# ProPrj_piezoAmpBoard_2024-09-30.net
KiCad netlist of a schematic drawn in EasyEDA Pro
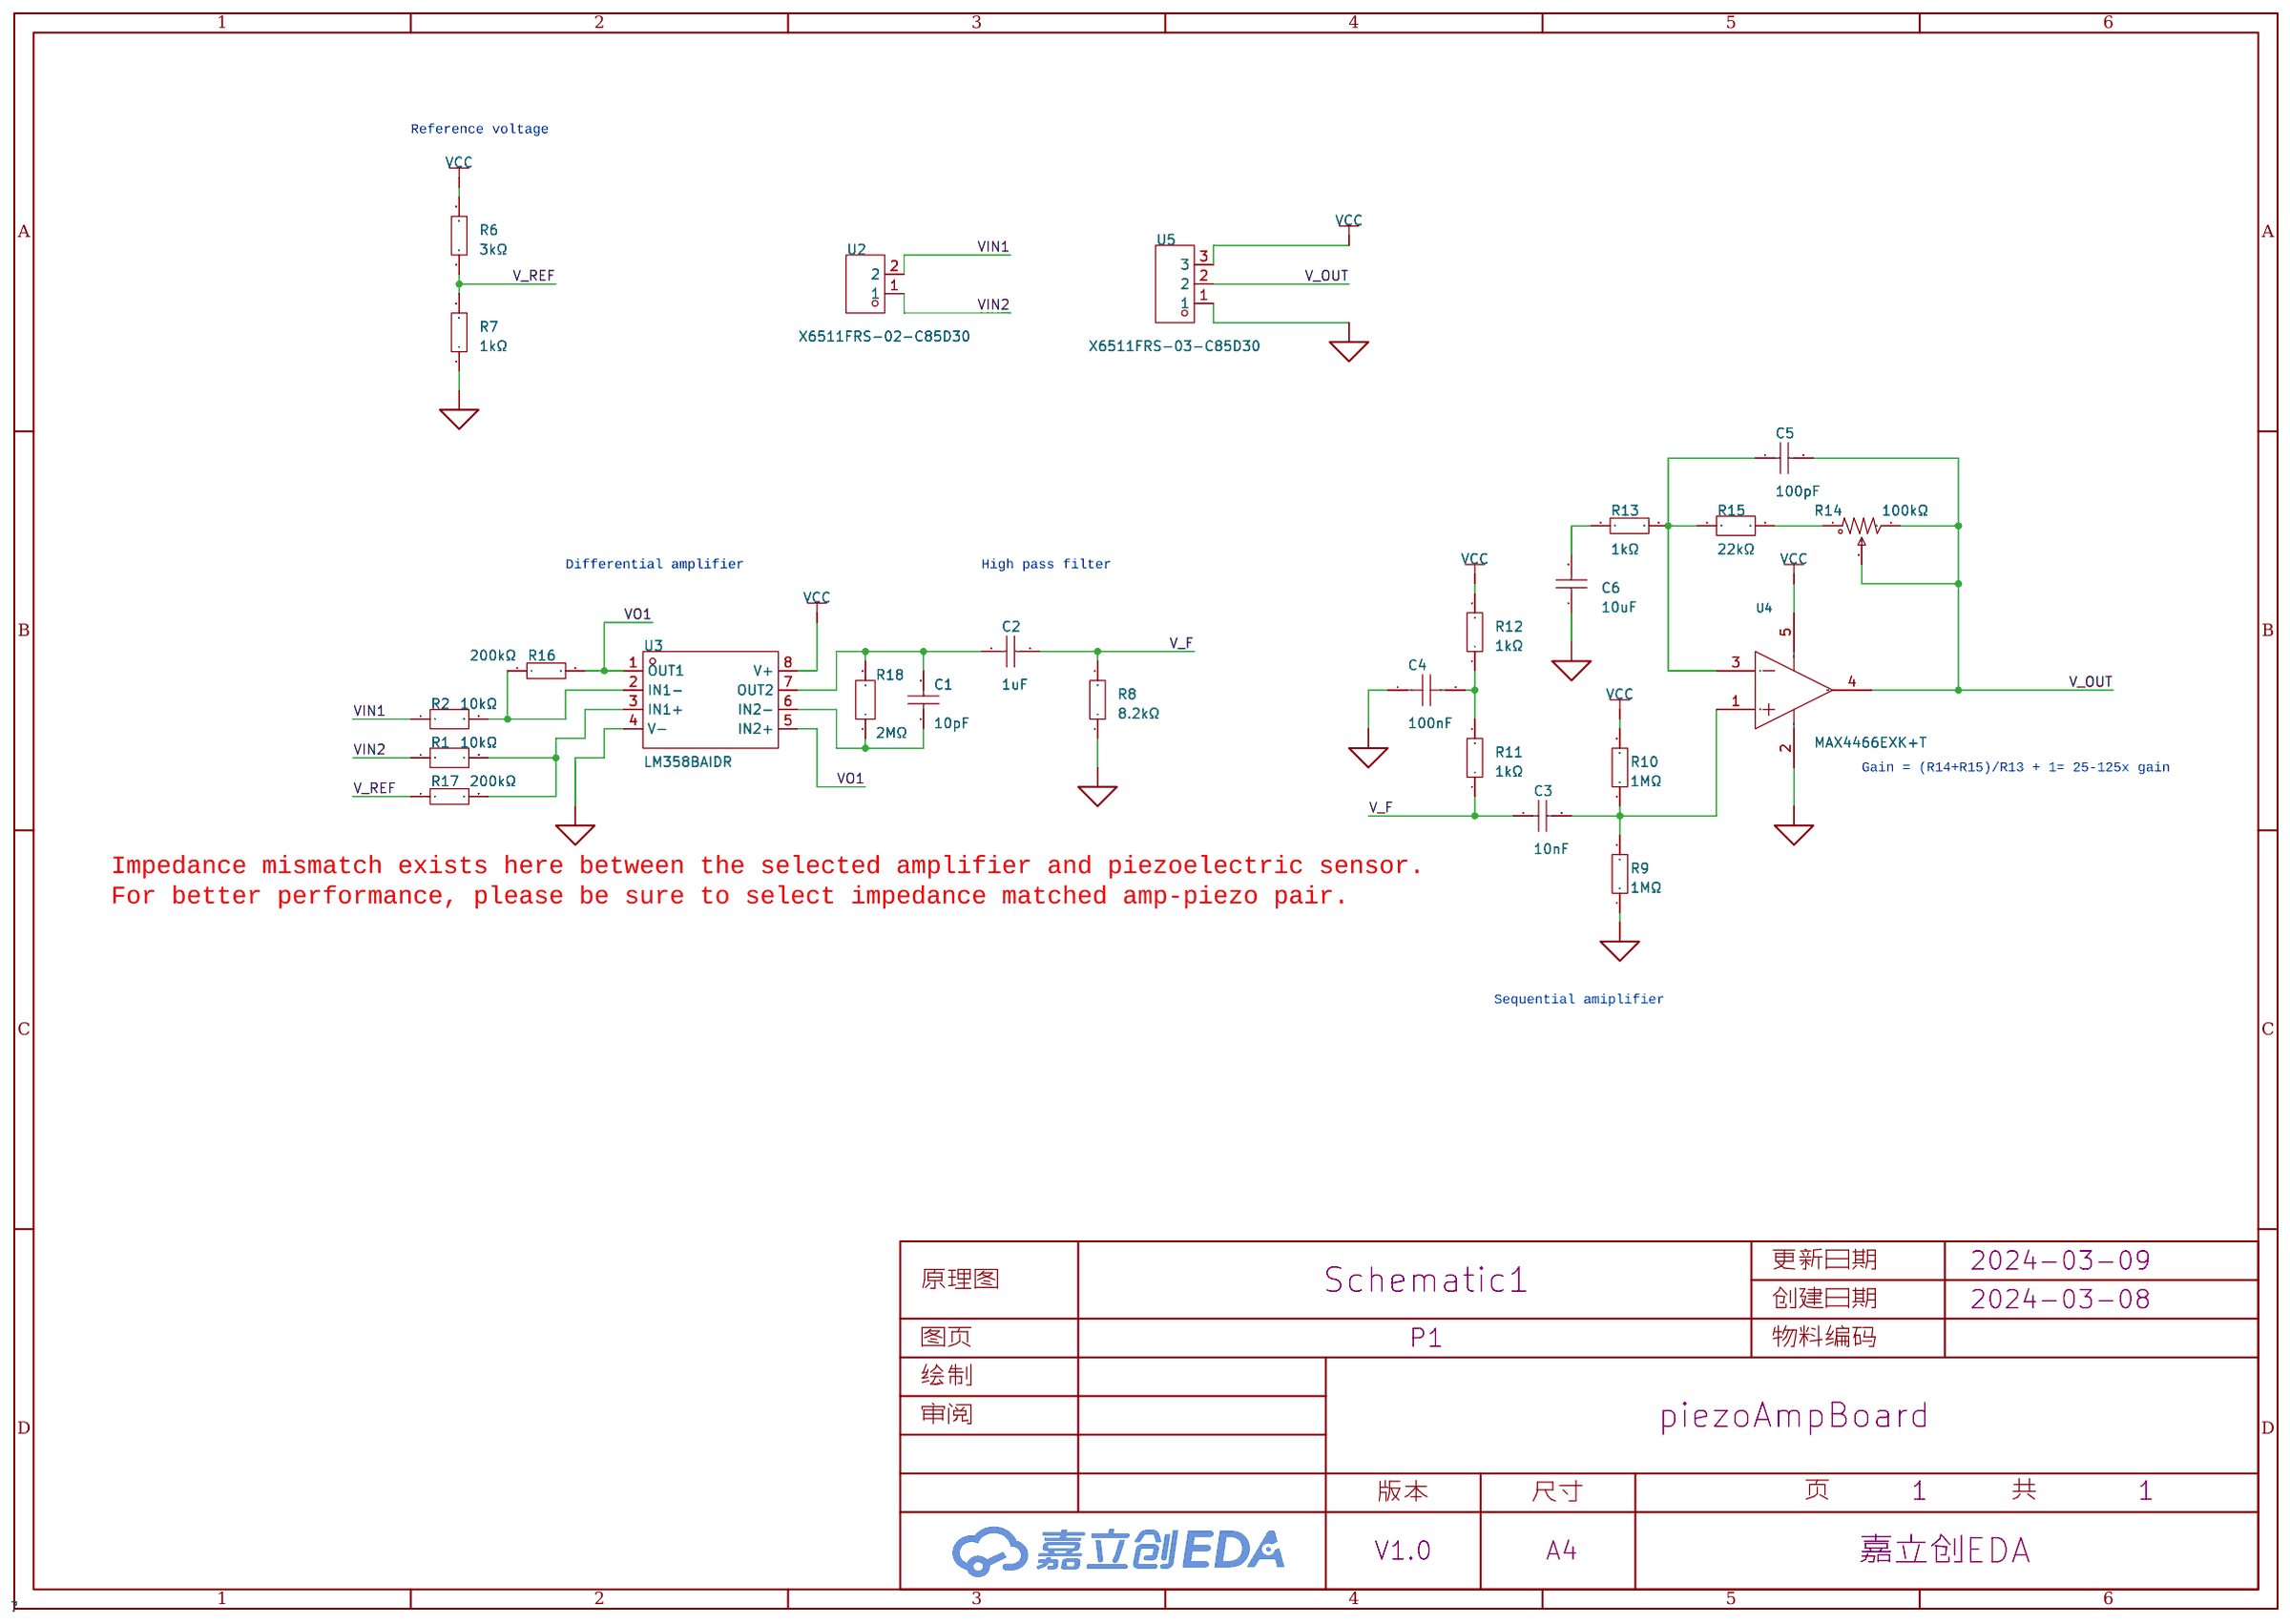
[diagram p0: schematic sheet]

(export (version "E")
  (design (tool "Eeschema 10.0.6"))
  (components
    (comp (ref "C1")
      (value "10pF")
      (footprint "easyedapro:C0402")
      (description "容值:10pF;精度:±5%;额定电压:50V;材质(温度系数):NP0;")
      (fields
        (field (name "Manufacturer Part") "CC0402JRNPO9BN100")
        (field (name "Manufacturer") "YAGEO(国巨)")
      )
      (libsource (lib "easyedapro") (part "CC0402JRNPO9BN100"))
    )
    (comp (ref "C2")
      (value "1uF")
      (footprint "easyedapro:C0402")
      (description "容值:1uF;精度:±10%;额定电压:10V;材质(温度系数):X5R;")
      (fields
        (field (name "Manufacturer Part") "CL05A105KP5NNNC")
        (field (name "Manufacturer") "SAMSUNG(三星)")
      )
      (libsource (lib "easyedapro") (part "CL05A105KP5NNNC"))
    )
    (comp (ref "C3")
      (value "10nF")
      (footprint "easyedapro:C0402")
      (description "容值:10nF;精度:±10%;额定电压:50V;材质(温度系数):X7R;")
      (fields
        (field (name "Manufacturer Part") "CC0402KRX7R9BB103")
        (field (name "Manufacturer") "YAGEO(国巨)")
      )
      (libsource (lib "easyedapro") (part "CC0402KRX7R9BB103"))
    )
    (comp (ref "C4")
      (value "100nF")
      (footprint "easyedapro:C0402")
      (description "容值:100nF;精度:±10%;额定电压:16V;材质(温度系数):X7R;")
      (fields
        (field (name "Manufacturer Part") "CC0402KRX7R7BB104")
        (field (name "Manufacturer") "YAGEO(国巨)")
      )
      (libsource (lib "easyedapro") (part "CC0402KRX7R7BB104"))
    )
    (comp (ref "C5")
      (value "100pF")
      (footprint "easyedapro:C0402")
      (description "容值:100pF;精度:±5%;额定电压:50V;材质(温度系数):C0G;")
      (fields
        (field (name "Manufacturer Part") "GRM1555C1H101JA01D")
        (field (name "Manufacturer") "muRata(村田)")
      )
      (libsource (lib "easyedapro") (part "GRM1555C1H101JA01D"))
    )
    (comp (ref "C6")
      (value "10uF")
      (footprint "easyedapro:C0402")
      (description "容值:10uF;精度:±20%;额定电压:6.3V;材质(温度系数):X5R;")
      (fields
        (field (name "Manufacturer Part") "GRM155R60J106ME44D")
        (field (name "Manufacturer") "muRata(村田)")
      )
      (libsource (lib "easyedapro") (part "GRM155R60J106ME44D"))
    )
    (comp (ref "R1")
      (value "10kΩ")
      (footprint "easyedapro:R0201")
      (description "电阻类型:厚膜电阻;阻值:10kΩ;精度:±1%;功率:50mW;最大工作电压:25V;温度系数:±200ppm/°C;")
      (fields
        (field (name "Manufacturer Part") "0201WMF1002TEE")
        (field (name "Manufacturer") "UNI-ROYAL(厚声)")
      )
      (libsource (lib "easyedapro") (part "0201WMF1002TEE"))
    )
    (comp (ref "R2")
      (value "10kΩ")
      (footprint "easyedapro:R0201")
      (description "电阻类型:厚膜电阻;阻值:10kΩ;精度:±1%;功率:50mW;最大工作电压:25V;温度系数:±200ppm/°C;")
      (fields
        (field (name "Manufacturer Part") "0201WMF1002TEE")
        (field (name "Manufacturer") "UNI-ROYAL(厚声)")
      )
      (libsource (lib "easyedapro") (part "0201WMF1002TEE"))
    )
    (comp (ref "R6")
      (value "3kΩ")
      (footprint "easyedapro:R0402")
      (description "电阻类型:厚膜电阻;阻值:3kΩ;精度:±1%;功率:62.5mW;最大工作电压:50V;温度系数:±100ppm/°C;")
      (fields
        (field (name "Manufacturer Part") "0402WGF3001TCE")
        (field (name "Manufacturer") "UNI-ROYAL(厚声)")
      )
      (libsource (lib "easyedapro") (part "0402WGF3001TCE"))
    )
    (comp (ref "R7")
      (value "1kΩ")
      (footprint "easyedapro:R0402")
      (description "电阻类型:厚膜电阻;阻值:1kΩ;精度:±1%;功率:62.5mW;最大工作电压:50V;温度系数:±100ppm/°C;")
      (fields
        (field (name "Manufacturer Part") "0402WGF1001TCE")
        (field (name "Manufacturer") "UNI-ROYAL(厚声)")
      )
      (libsource (lib "easyedapro") (part "0402WGF1001TCE"))
    )
    (comp (ref "R8")
      (value "8.2kΩ")
      (footprint "easyedapro:R0402")
      (description "电阻类型:厚膜电阻;阻值:8.2kΩ;精度:±1%;功率:62.5mW;最大工作电压:50V;温度系数:±100ppm/°C;")
      (fields
        (field (name "Manufacturer Part") "0402WGF8201TCE")
        (field (name "Manufacturer") "UNI-ROYAL(厚声)")
      )
      (libsource (lib "easyedapro") (part "0402WGF8201TCE"))
    )
    (comp (ref "R9")
      (value "1MΩ")
      (footprint "easyedapro:R0201")
      (description "电阻类型:厚膜电阻;阻值:1MΩ;精度:±1%;功率:50mW;最大工作电压:25V;温度系数:±200ppm/°C;")
      (fields (field (name "Manufacturer Part") "RC0201FR-071ML") (field (name "Manufacturer") "YAGEO(国巨)"))
      (libsource (lib "easyedapro") (part "RC0201FR-071ML"))
    )
    (comp (ref "R10")
      (value "1MΩ")
      (footprint "easyedapro:R0201")
      (description "电阻类型:厚膜电阻;阻值:1MΩ;精度:±1%;功率:50mW;最大工作电压:25V;温度系数:±200ppm/°C;")
      (fields (field (name "Manufacturer Part") "RC0201FR-071ML") (field (name "Manufacturer") "YAGEO(国巨)"))
      (libsource (lib "easyedapro") (part "RC0201FR-071ML"))
    )
    (comp (ref "R11")
      (value "1kΩ")
      (footprint "easyedapro:R0201")
      (description "电阻类型:厚膜电阻;阻值:1kΩ;精度:±1%;功率:50mW;最大工作电压:25V;温度系数:±200ppm/°C;")
      (fields
        (field (name "Manufacturer Part") "0201WMF1001TEE")
        (field (name "Manufacturer") "UNI-ROYAL(厚声)")
      )
      (libsource (lib "easyedapro") (part "0201WMF1001TEE"))
    )
    (comp (ref "R12")
      (value "1kΩ")
      (footprint "easyedapro:R0201")
      (description "电阻类型:厚膜电阻;阻值:1kΩ;精度:±1%;功率:50mW;最大工作电压:25V;温度系数:±200ppm/°C;")
      (fields
        (field (name "Manufacturer Part") "0201WMF1001TEE")
        (field (name "Manufacturer") "UNI-ROYAL(厚声)")
      )
      (libsource (lib "easyedapro") (part "0201WMF1001TEE"))
    )
    (comp (ref "R13")
      (value "1kΩ")
      (footprint "easyedapro:R0201")
      (description "电阻类型:厚膜电阻;阻值:1kΩ;精度:±1%;功率:50mW;最大工作电压:25V;温度系数:±200ppm/°C;")
      (fields
        (field (name "Manufacturer Part") "0201WMF1001TEE")
        (field (name "Manufacturer") "UNI-ROYAL(厚声)")
      )
      (libsource (lib "easyedapro") (part "0201WMF1001TEE"))
    )
    (comp (ref "R14")
      (value "100kΩ")
      (footprint "easyedapro:RES-ADJ-SMD_TC33X-2-104E")
      (description "阻值:100kΩ;精度:±25%;功率:150mW;温度系数:±250ppm/°C;")
      (fields (field (name "Manufacturer Part") "TC33X-2-104E") (field (name "Manufacturer") "BOURNS"))
      (libsource (lib "easyedapro") (part "TC33X-2-104E"))
    )
    (comp (ref "R15")
      (value "22kΩ")
      (footprint "easyedapro:R0201")
      (description "电阻类型:厚膜电阻;阻值:22kΩ;精度:±1%;功率:50mW;最大工作电压:25V;温度系数:±200ppm/°C;")
      (fields (field (name "Manufacturer Part") "RC0201FR-0722KL") (field (name "Manufacturer") "YAGEO(国巨)"))
      (libsource (lib "easyedapro") (part "RC0201FR-0722KL"))
    )
    (comp (ref "R16")
      (value "200kΩ")
      (footprint "easyedapro:R0201")
      (description "电阻类型:厚膜电阻;阻值:200kΩ;精度:±1%;功率:50mW;最大工作电压:25V;温度系数:±200ppm/°C;")
      (fields (field (name "Manufacturer Part") "RC0201FR-07200KL") (field (name "Manufacturer") "YAGEO(国巨)"))
      (libsource (lib "easyedapro") (part "RC0201FR-07200KL"))
    )
    (comp (ref "R17")
      (value "200kΩ")
      (footprint "easyedapro:R0201")
      (description "电阻类型:厚膜电阻;阻值:200kΩ;精度:±1%;功率:50mW;最大工作电压:25V;温度系数:±200ppm/°C;")
      (fields (field (name "Manufacturer Part") "RC0201FR-07200KL") (field (name "Manufacturer") "YAGEO(国巨)"))
      (libsource (lib "easyedapro") (part "RC0201FR-07200KL"))
    )
    (comp (ref "R18")
      (value "2MΩ")
      (footprint "easyedapro:R0201")
      (description "电阻类型:厚膜电阻;阻值:2MΩ;精度:±1%;功率:50mW;最大工作电压:25V;温度系数:±200ppm/°C;")
      (fields
        (field (name "Manufacturer Part") "0201WMF2004TEE")
        (field (name "Manufacturer") "UNI-ROYAL(厚声)")
      )
      (libsource (lib "easyedapro") (part "0201WMF2004TEE"))
    )
    (comp (ref "U2")
      (value "X6511FRS-02-C85D30")
      (footprint "easyedapro:HDR-SMD_2P-P2.54-H-F-L11.5")
      (description "插孔结构:1x2P;间距:2.54mm;安装类型:卧贴;排数:单排;总孔位数:2P;塑高:8.5mm;")
      (fields (field (name "Manufacturer") "XKB Connectivity(中国星坤)"))
      (libsource (lib "easyedapro") (part "X6511FRS-02-C85D30"))
    )
    (comp (ref "U3")
      (value "LM358BAIDR")
      (footprint "easyedapro:SOIC-8_L4.9-W3.9-P1.27-LS6.0-BL")
      (description "放大器数:双路;增益带宽积(GBP):1.2MHz;输入偏置电流(Ib):10nA;压摆率(SR):0.5V/us;带宽(-3db):-;")
      (fields (field (name "Manufacturer") "TI(德州仪器)"))
      (libsource (lib "easyedapro") (part "LM358BAIDR"))
    )
    (comp (ref "U4")
      (value "MAX4466EXK+T")
      (footprint "easyedapro:SC-70-5_L2.0-W1.3-P0.65-LS2.1-BR")
      (description "功放类型:-;扬声器通道数:单声道;输出功率:-;静态电流(Iq):-;")
      (fields (field (name "Manufacturer") "ADI(亚德诺)/MAXIM(美信)"))
      (libsource (lib "easyedapro") (part "MAX4466EXK+T"))
    )
    (comp (ref "U5")
      (value "X6511FRS-03-C85D30")
      (footprint "easyedapro:HDR-SMD_3P-P2.54-H-F-L11.5")
      (description "插孔结构:1x3P;间距:2.54mm;安装类型:卧贴;排数:单排;总孔位数:3P;塑高:8.5mm;")
      (fields (field (name "Manufacturer") "XKB Connectivity(中国星坤)"))
      (libsource (lib "easyedapro") (part "X6511FRS-03-C85D30"))
    )
  )
  (nets
    (net (code "1") (name "/VIN1") (class "Default")
      (node (ref "R2") (pin "1") (pinfunction "1_1") (pintype "unspecified"))
      (node (ref "U2") (pin "2") (pinfunction "2_2") (pintype "unspecified"))
    )
    (net (code "2") (name "/VIN2") (class "Default")
      (node (ref "R1") (pin "1") (pinfunction "1_1") (pintype "unspecified"))
      (node (ref "U2") (pin "1") (pinfunction "1_1") (pintype "unspecified"))
    )
    (net (code "3") (name "/VO1") (class "Default")
      (node (ref "R16") (pin "2") (pinfunction "2_2") (pintype "input"))
      (node (ref "U3") (pin "1") (pinfunction "OUT1_1") (pintype "unspecified"))
      (node (ref "U3") (pin "5") (pinfunction "IN2+_5") (pintype "unspecified"))
    )
    (net (code "4") (name "/V_F") (class "Default")
      (node (ref "C2") (pin "2") (pinfunction "2_2") (pintype "input"))
      (node (ref "C3") (pin "1") (pinfunction "1_1") (pintype "input"))
      (node (ref "R11") (pin "1") (pinfunction "1_1") (pintype "unspecified"))
      (node (ref "R8") (pin "2") (pinfunction "2_2") (pintype "input"))
    )
    (net (code "5") (name "/V_OUT") (class "Default")
      (node (ref "C5") (pin "2") (pinfunction "2_2") (pintype "input"))
      (node (ref "R14") (pin "2") (pinfunction "2_2") (pintype "input"))
      (node (ref "R14") (pin "3") (pinfunction "3_3") (pintype "input"))
      (node (ref "U4") (pin "4") (pinfunction "OUT_4") (pintype "output"))
      (node (ref "U5") (pin "2") (pinfunction "2_2") (pintype "unspecified"))
    )
    (net (code "6") (name "/V_REF") (class "Default")
      (node (ref "R17") (pin "1") (pinfunction "1_1") (pintype "input"))
      (node (ref "R6") (pin "1") (pinfunction "1_1") (pintype "input"))
      (node (ref "R7") (pin "2") (pinfunction "2_2") (pintype "input"))
    )
    (net (code "7") (name "AGND") (class "Default")
      (node (ref "C4") (pin "1") (pinfunction "1_1") (pintype "unspecified"))
      (node (ref "C6") (pin "1") (pinfunction "1_1") (pintype "input"))
      (node (ref "R7") (pin "1") (pinfunction "1_1") (pintype "input"))
      (node (ref "R8") (pin "1") (pinfunction "1_1") (pintype "input"))
      (node (ref "R9") (pin "1") (pinfunction "1_1") (pintype "unspecified"))
      (node (ref "U3") (pin "4") (pinfunction "V-_4") (pintype "unspecified"))
      (node (ref "U4") (pin "2") (pinfunction "GND_2") (pintype "input"))
      (node (ref "U5") (pin "1") (pinfunction "1_1") (pintype "unspecified"))
    )
    (net (code "8") (name "Net-(C4-Pad2)") (class "Default")
      (node (ref "C4") (pin "2") (pinfunction "2_2") (pintype "unspecified"))
      (node (ref "R11") (pin "2") (pinfunction "2_2") (pintype "unspecified"))
      (node (ref "R12") (pin "1") (pinfunction "1_1") (pintype "unspecified"))
    )
    (net (code "9") (name "Net-(C6-Pad2)") (class "Default")
      (node (ref "C6") (pin "2") (pinfunction "2_2") (pintype "input"))
      (node (ref "R13") (pin "1") (pinfunction "1_1") (pintype "unspecified"))
    )
    (net (code "10") (name "Net-(R14-Pad1)") (class "Default")
      (node (ref "R14") (pin "1") (pinfunction "1_1") (pintype "input"))
      (node (ref "R15") (pin "2") (pinfunction "2_2") (pintype "unspecified"))
    )
    (net (code "11") (name "Net-(U3-IN1+)") (class "Default")
      (node (ref "R1") (pin "2") (pinfunction "2_2") (pintype "unspecified"))
      (node (ref "R17") (pin "2") (pinfunction "2_2") (pintype "input"))
      (node (ref "U3") (pin "3") (pinfunction "IN1+_3") (pintype "unspecified"))
    )
    (net (code "12") (name "Net-(U3-IN1-)") (class "Default")
      (node (ref "R16") (pin "1") (pinfunction "1_1") (pintype "input"))
      (node (ref "R2") (pin "2") (pinfunction "2_2") (pintype "unspecified"))
      (node (ref "U3") (pin "2") (pinfunction "IN1-_2") (pintype "unspecified"))
    )
    (net (code "13") (name "Net-(U3-IN2-)") (class "Default")
      (node (ref "C1") (pin "1") (pinfunction "1_1") (pintype "input"))
      (node (ref "R18") (pin "1") (pinfunction "1_1") (pintype "unspecified"))
      (node (ref "U3") (pin "6") (pinfunction "IN2-_6") (pintype "unspecified"))
    )
    (net (code "14") (name "Net-(U3-OUT2)") (class "Default")
      (node (ref "C1") (pin "2") (pinfunction "2_2") (pintype "input"))
      (node (ref "C2") (pin "1") (pinfunction "1_1") (pintype "input"))
      (node (ref "R18") (pin "2") (pinfunction "2_2") (pintype "unspecified"))
      (node (ref "U3") (pin "7") (pinfunction "OUT2_7") (pintype "unspecified"))
    )
    (net (code "15") (name "Net-(U4-IN+)") (class "Default")
      (node (ref "C3") (pin "2") (pinfunction "2_2") (pintype "input"))
      (node (ref "R10") (pin "1") (pinfunction "1_1") (pintype "unspecified"))
      (node (ref "R9") (pin "2") (pinfunction "2_2") (pintype "unspecified"))
      (node (ref "U4") (pin "1") (pinfunction "IN+_1") (pintype "input"))
    )
    (net (code "16") (name "Net-(U4-IN-)") (class "Default")
      (node (ref "C5") (pin "1") (pinfunction "1_1") (pintype "input"))
      (node (ref "R13") (pin "2") (pinfunction "2_2") (pintype "unspecified"))
      (node (ref "R15") (pin "1") (pinfunction "1_1") (pintype "unspecified"))
      (node (ref "U4") (pin "3") (pinfunction "IN-_3") (pintype "input"))
    )
    (net (code "17") (name "VCC") (class "Default")
      (node (ref "R10") (pin "2") (pinfunction "2_2") (pintype "unspecified"))
      (node (ref "R12") (pin "2") (pinfunction "2_2") (pintype "unspecified"))
      (node (ref "R6") (pin "2") (pinfunction "2_2") (pintype "input"))
      (node (ref "U3") (pin "8") (pinfunction "V+_8") (pintype "unspecified"))
      (node (ref "U4") (pin "5") (pinfunction "VCC_5") (pintype "input"))
      (node (ref "U5") (pin "3") (pinfunction "3_3") (pintype "unspecified"))
    )
  )
)
